# Filter_Capacitors_-_FOTA_Digital_ICSP.net
KiCad netlist of a schematic drawn in Altium Designer
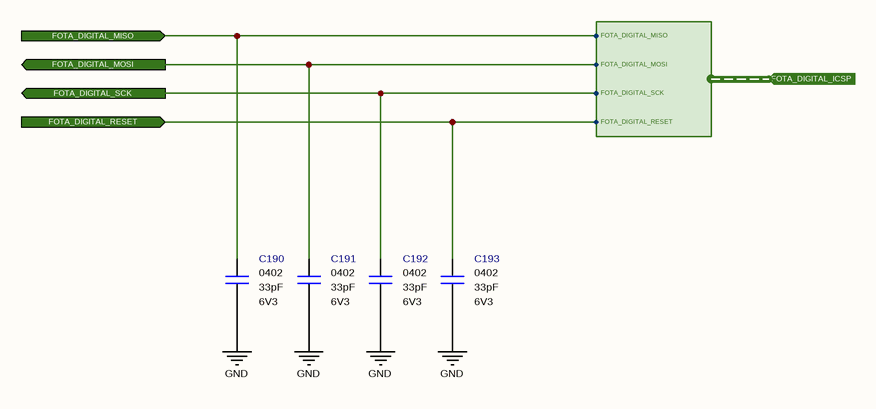
[diagram p0: Filter Capacitors - FOTA Digital ICSP.SchDoc]

(export (version "E")
  (design (tool "Eeschema 10.0.6"))
  (components
    (comp (ref "C190")
      (value "33pF")
      (footprint "CAPACITOR_0402")
      (description "Capacitor - 33pF [0402] (Ceramic)")
      (fields
        (field (name "TOLERANCE") "10%")
        (field (name "CASE") "0402")
        (field (name "VOLTAGE") "6V3")
        (field (name "MANUFACTURER PART NUMBER") "C0402C330J9RACAUTO")
      )
      (libsource (lib "Ovoo_Library") (part "Capacitor - 33pF [0402-6V3]"))
    )
    (comp (ref "C191")
      (value "33pF")
      (footprint "CAPACITOR_0402")
      (description "Capacitor - 33pF [0402] (Ceramic)")
      (fields
        (field (name "TOLERANCE") "10%")
        (field (name "CASE") "0402")
        (field (name "VOLTAGE") "6V3")
        (field (name "MANUFACTURER PART NUMBER") "C0402C330J9RACAUTO")
      )
      (libsource (lib "Ovoo_Library") (part "Capacitor - 33pF [0402-6V3]"))
    )
    (comp (ref "C192")
      (value "33pF")
      (footprint "CAPACITOR_0402")
      (description "Capacitor - 33pF [0402] (Ceramic)")
      (fields
        (field (name "TOLERANCE") "10%")
        (field (name "CASE") "0402")
        (field (name "VOLTAGE") "6V3")
        (field (name "MANUFACTURER PART NUMBER") "C0402C330J9RACAUTO")
      )
      (libsource (lib "Ovoo_Library") (part "Capacitor - 33pF [0402-6V3]"))
    )
    (comp (ref "C193")
      (value "33pF")
      (footprint "CAPACITOR_0402")
      (description "Capacitor - 33pF [0402] (Ceramic)")
      (fields
        (field (name "TOLERANCE") "10%")
        (field (name "CASE") "0402")
        (field (name "VOLTAGE") "6V3")
        (field (name "MANUFACTURER PART NUMBER") "C0402C330J9RACAUTO")
      )
      (libsource (lib "Ovoo_Library") (part "Capacitor - 33pF [0402-6V3]"))
    )
  )
  (nets
    (net (code "2") (name "/FOTA_DIGITAL_MISO") (class "Default")
      (node (ref "C190") (pin "2") (pinfunction "2_2") (pintype "passive"))
    )
    (net (code "3") (name "/FOTA_DIGITAL_MOSI") (class "Default")
      (node (ref "C191") (pin "2") (pinfunction "2_2") (pintype "passive"))
    )
    (net (code "4") (name "/FOTA_DIGITAL_RESET") (class "Default")
      (node (ref "C193") (pin "2") (pinfunction "2_2") (pintype "passive"))
    )
    (net (code "5") (name "/FOTA_DIGITAL_SCK") (class "Default")
      (node (ref "C192") (pin "2") (pinfunction "2_2") (pintype "passive"))
    )
    (net (code "7") (name "GND") (class "Default")
      (node (ref "C190") (pin "1") (pinfunction "1_1") (pintype "passive"))
      (node (ref "C191") (pin "1") (pinfunction "1_1") (pintype "passive"))
      (node (ref "C192") (pin "1") (pinfunction "1_1") (pintype "passive"))
      (node (ref "C193") (pin "1") (pinfunction "1_1") (pintype "passive"))
    )
  )
)
